# 04_PCIe.net
KiCad netlist of a schematic drawn in Altium Designer
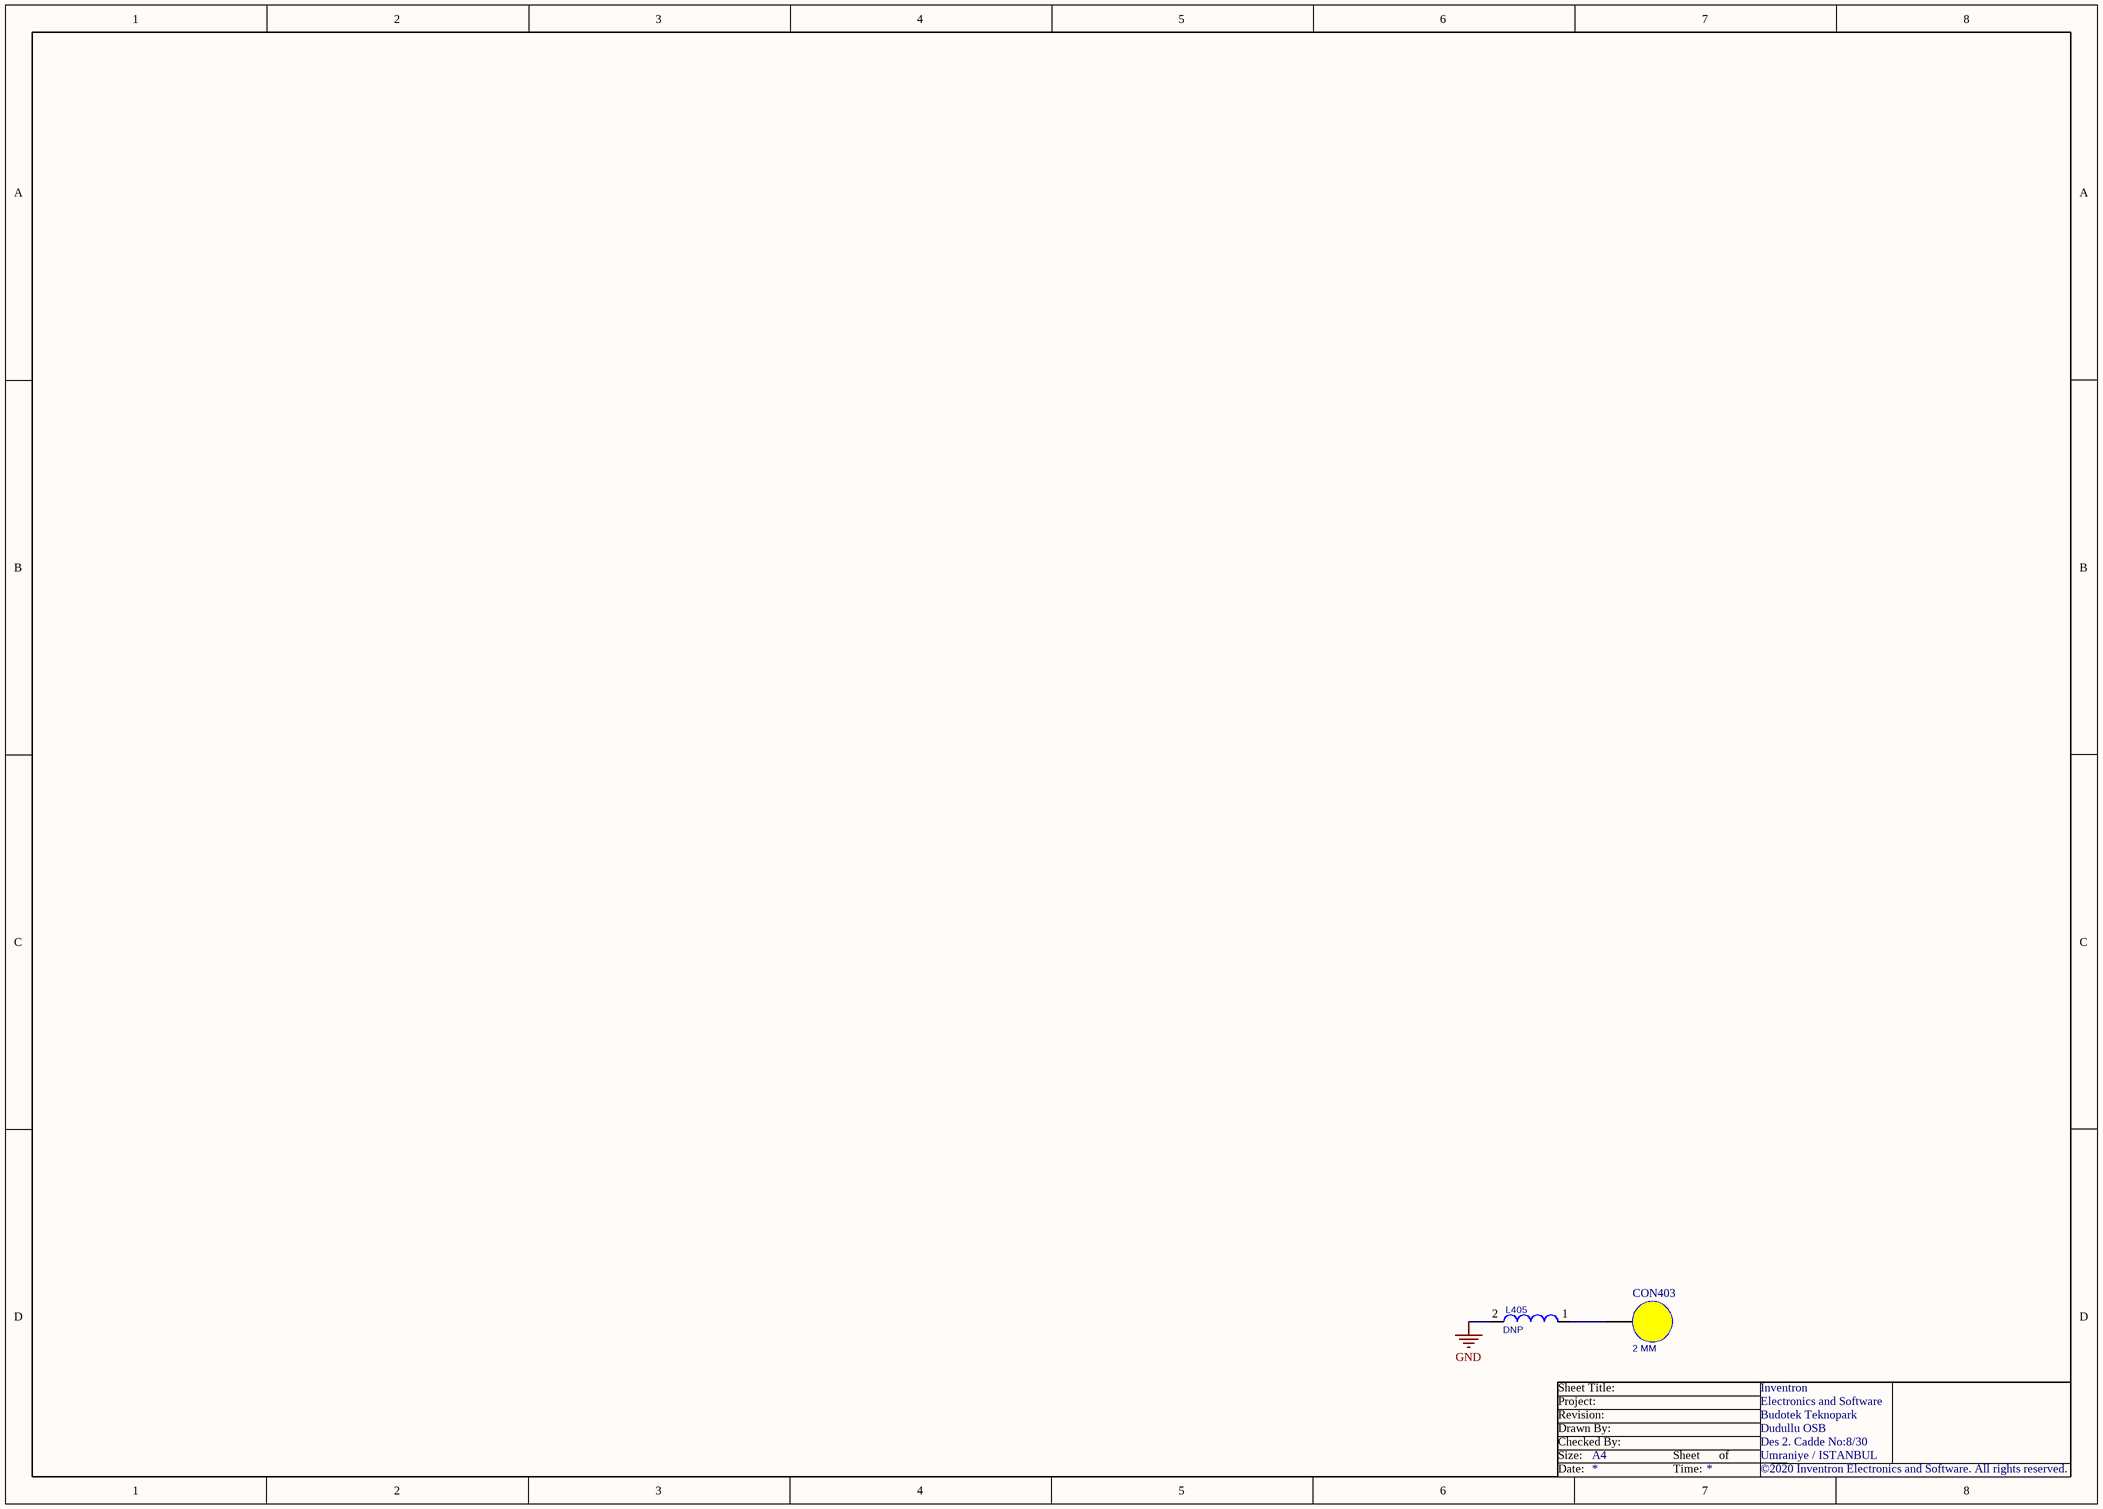
[diagram p0: 04 PCIe.SchDoc]

(export (version "E")
  (design (tool "Eeschema 10.0.6"))
  (components
    (comp (ref "CON403")
      (value "2 MM")
      (footprint "9774045243R")
      (description "Round Standoff Threaded M2x0.4 Steel 0.177\" (4.50mm)")
      (fields (field (name "CREATED BY") "EE") (field (name "CHECKED BY") "*"))
      (libsource (lib "ARETE_SCH") (part "CON-9774045243R"))
    )
    (comp (ref "L405")
      (value "FERRITE 0603")
      (footprint "0603_RES")
      (description "FERRITE BEAD 0603")
      (fields (field (name "ASSY_OPT") "DNP") (field (name "CHECKED BY") "*"))
      (libsource (lib "ARETE_L") (part "IND-FERRITE 0603"))
    )
  )
  (nets
    (net (code "1") (name "GND") (class "Default")
      (node (ref "L405") (pin "2") (pinfunction "2_2") (pintype "passive"))
    )
    (net (code "2") (name "Net-(CON403-0)") (class "Default")
      (node (ref "CON403") (pin "1") (pinfunction "0_1") (pintype "passive"))
      (node (ref "L405") (pin "1") (pinfunction "1_1") (pintype "passive"))
    )
  )
)
